# Open_Flight_Controller.net
KiCad netlist of a schematic drawn in EAGLE
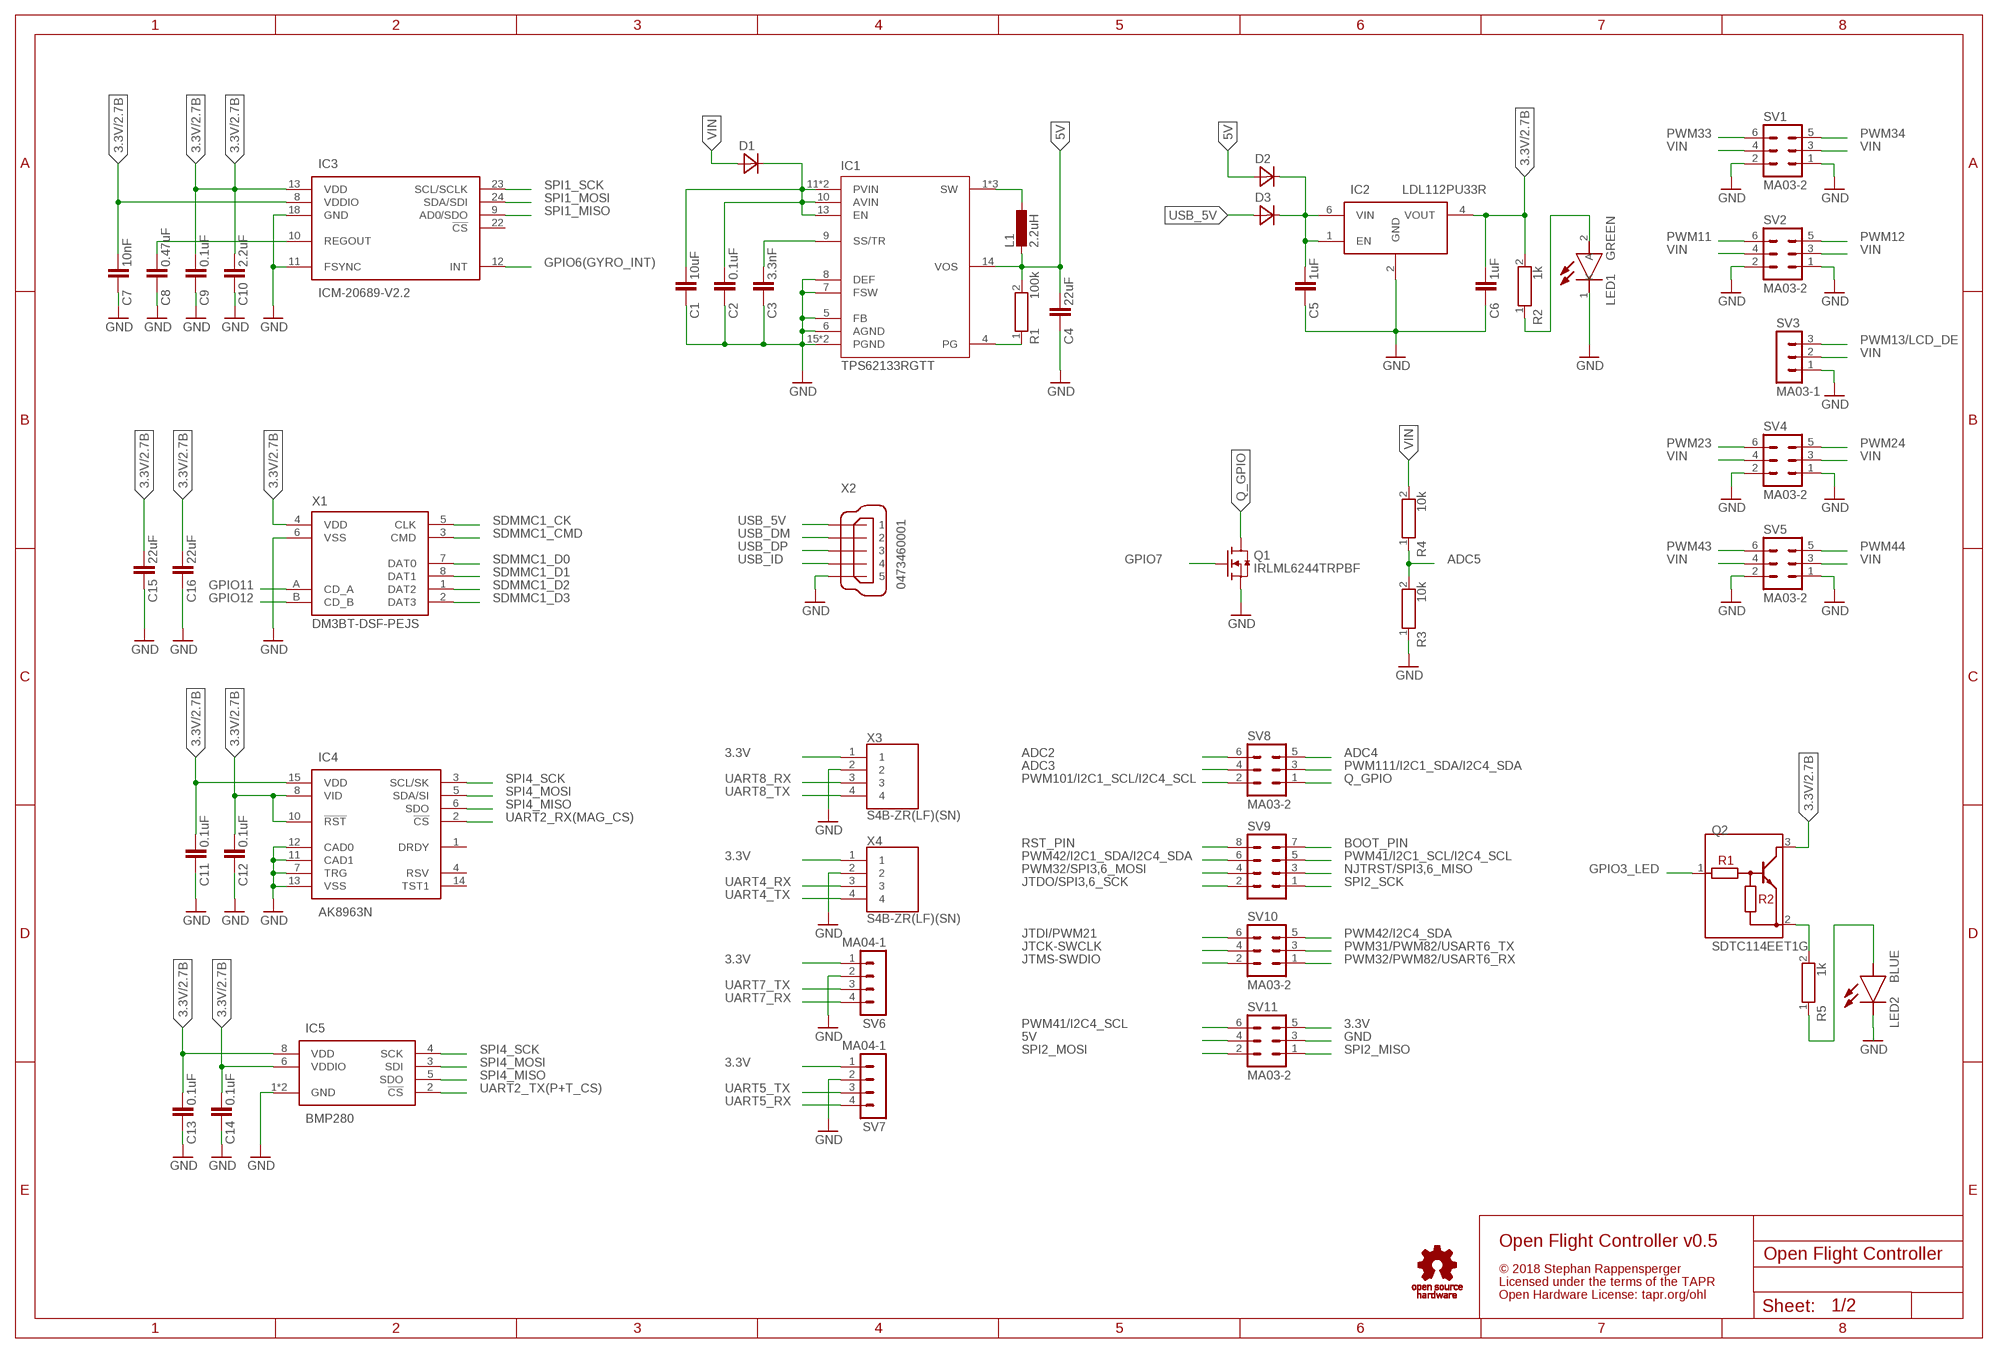
[diagram p0: schematic, sheet 1]
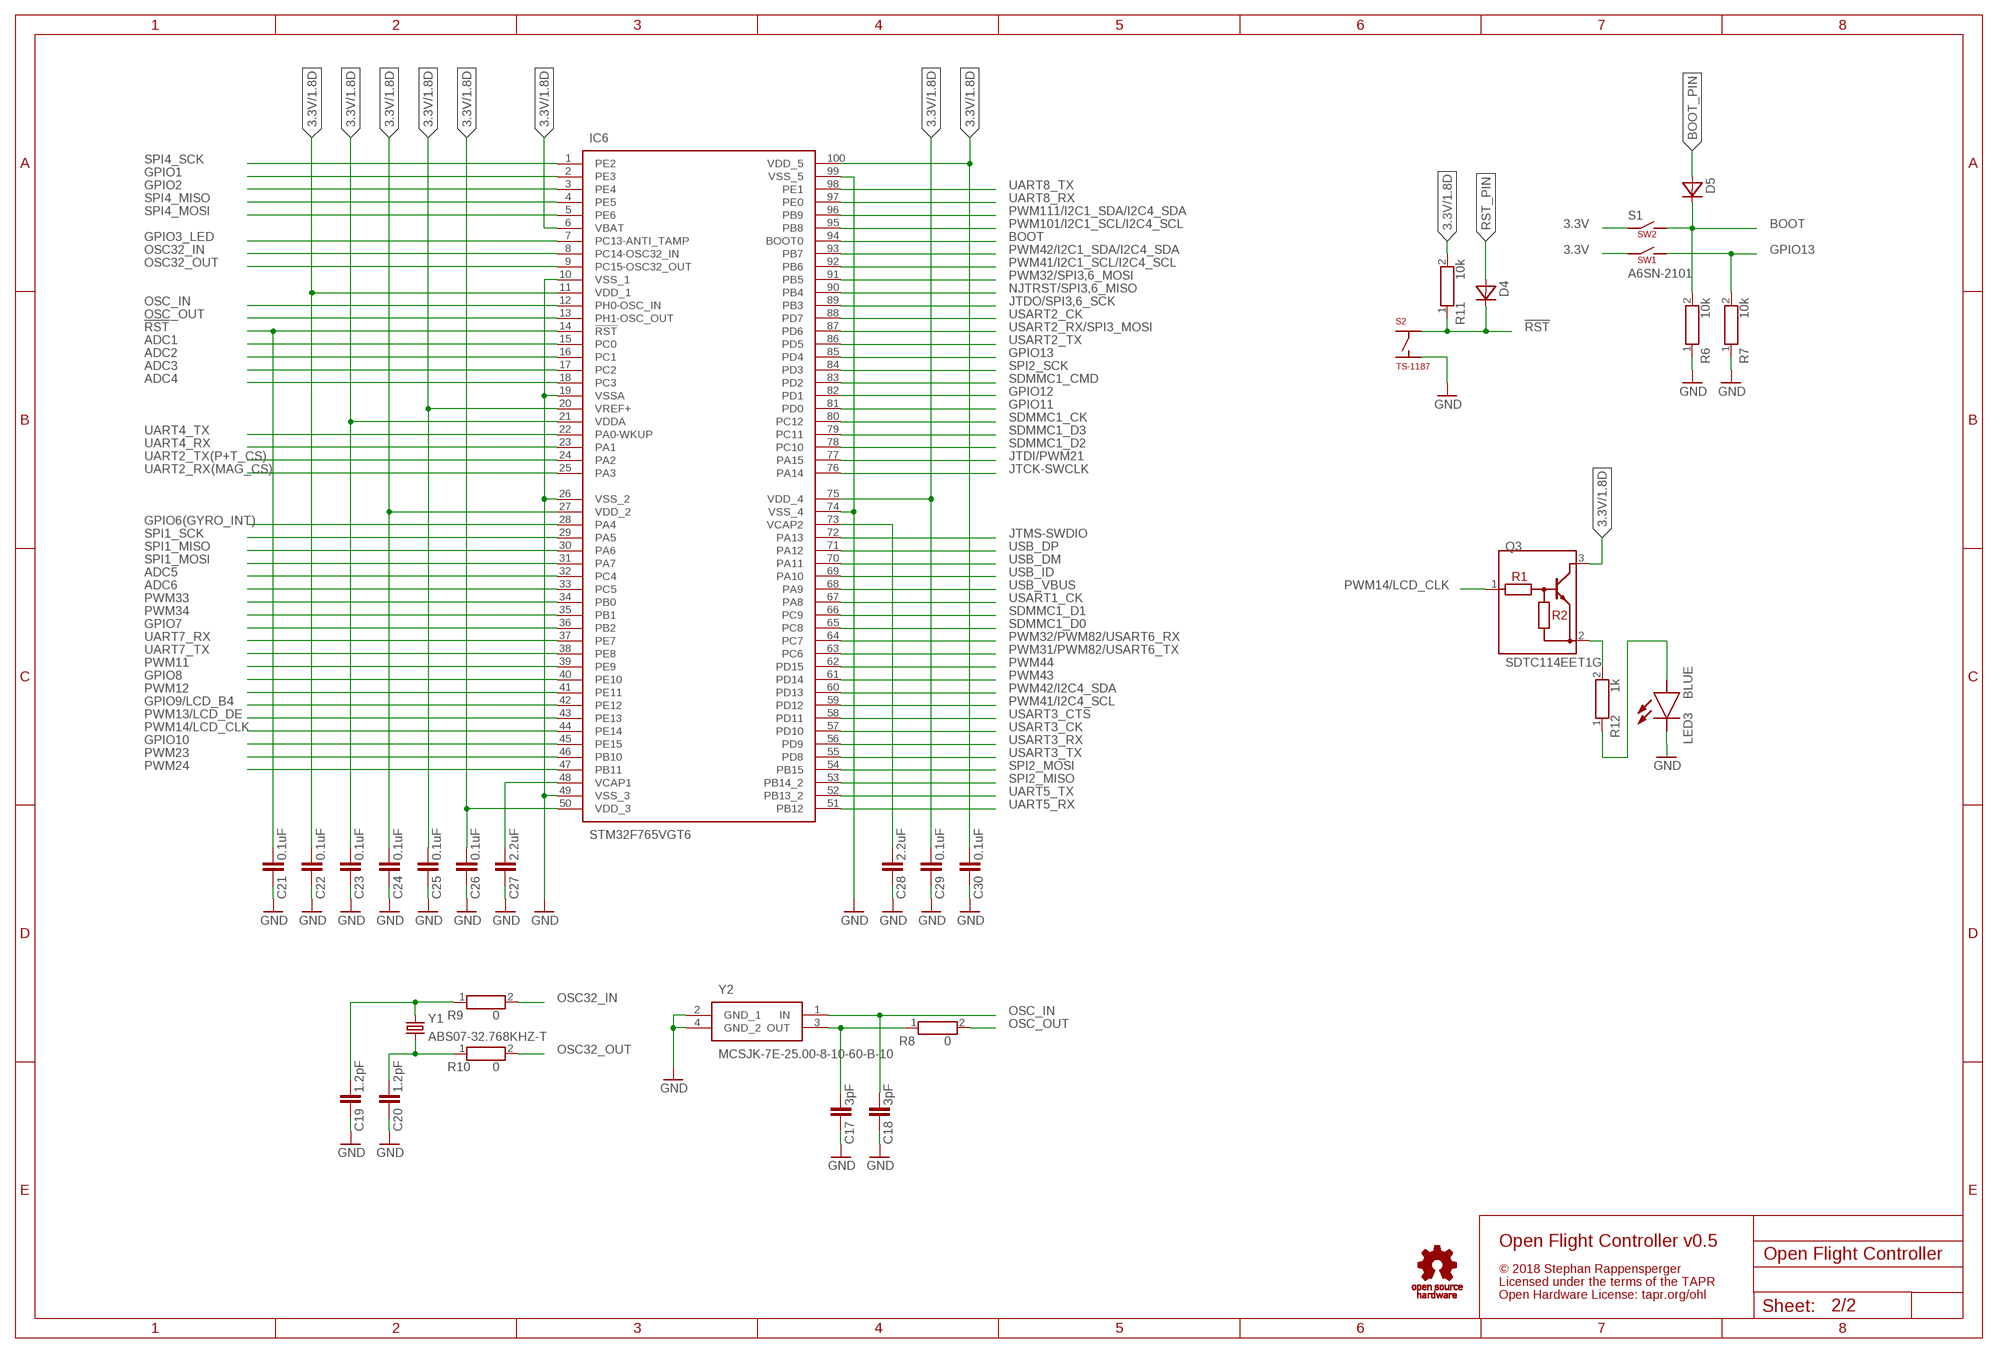
[diagram p1: schematic, sheet 2]

(export (version "E")
  (design (tool "Eeschema 10.0.6"))
  (components
    (comp (ref "C17")
      (value "3pF")
      (footprint "eagle-import:CAPC1608X90N")
      (fields
        (field (name "ARROW_PART_NUMBER") "GRM188R71C105KA12D")
        (field (name "RS_PART_NUMBER") "1448491")
      )
      (libsource (lib "eagle-import") (part "GRM188R71C105KA12D"))
    )
    (comp (ref "C18")
      (value "3pF")
      (footprint "eagle-import:CAPC1608X90N")
      (fields
        (field (name "ARROW_PART_NUMBER") "GRM188R71C105KA12D")
        (field (name "RS_PART_NUMBER") "1448491")
      )
      (libsource (lib "eagle-import") (part "GRM188R71C105KA12D"))
    )
    (comp (ref "C19")
      (value "1.2pF")
      (footprint "eagle-import:CAPC1608X90N")
      (fields
        (field (name "ARROW_PART_NUMBER") "GRM188R71C105KA12D")
        (field (name "RS_PART_NUMBER") "1448491")
      )
      (libsource (lib "eagle-import") (part "GRM188R71C105KA12D"))
    )
    (comp (ref "C20")
      (value "1.2pF")
      (footprint "eagle-import:CAPC1608X90N")
      (fields
        (field (name "ARROW_PART_NUMBER") "GRM188R71C105KA12D")
        (field (name "RS_PART_NUMBER") "1448491")
      )
      (libsource (lib "eagle-import") (part "GRM188R71C105KA12D"))
    )
    (comp (ref "C21")
      (value "0.1uF")
      (footprint "eagle-import:CAPC1608X90N")
      (fields
        (field (name "ARROW_PART_NUMBER") "GRM188R71H104KA93D")
        (field (name "RS_PART_NUMBER") "6242480P")
      )
      (libsource (lib "eagle-import") (part "GRM188R71H104KA93D"))
    )
    (comp (ref "C22")
      (value "0.1uF")
      (footprint "eagle-import:CAPC1608X90N")
      (fields
        (field (name "ARROW_PART_NUMBER") "GRM188R71H104KA93D")
        (field (name "RS_PART_NUMBER") "6242480P")
      )
      (libsource (lib "eagle-import") (part "GRM188R71H104KA93D"))
    )
    (comp (ref "C23")
      (value "0.1uF")
      (footprint "eagle-import:CAPC1608X90N")
      (fields
        (field (name "ARROW_PART_NUMBER") "GRM188R71H104KA93D")
        (field (name "RS_PART_NUMBER") "6242480P")
      )
      (libsource (lib "eagle-import") (part "GRM188R71H104KA93D"))
    )
    (comp (ref "C24")
      (value "0.1uF")
      (footprint "eagle-import:CAPC1608X90N")
      (fields
        (field (name "ARROW_PART_NUMBER") "GRM188R71H104KA93D")
        (field (name "RS_PART_NUMBER") "6242480P")
      )
      (libsource (lib "eagle-import") (part "GRM188R71H104KA93D"))
    )
    (comp (ref "C25")
      (value "0.1uF")
      (footprint "eagle-import:CAPC1608X90N")
      (fields
        (field (name "ARROW_PART_NUMBER") "GRM188R71H104KA93D")
        (field (name "RS_PART_NUMBER") "6242480P")
      )
      (libsource (lib "eagle-import") (part "GRM188R71H104KA93D"))
    )
    (comp (ref "C26")
      (value "0.1uF")
      (footprint "eagle-import:CAPC1608X90N")
      (fields
        (field (name "ARROW_PART_NUMBER") "GRM188R71H104KA93D")
        (field (name "RS_PART_NUMBER") "6242480P")
      )
      (libsource (lib "eagle-import") (part "GRM188R71H104KA93D"))
    )
    (comp (ref "C27")
      (value "2.2uF")
      (footprint "eagle-import:CAPC1608X90N")
      (fields
        (field (name "ARROW_PART_NUMBER") "GRM188R71A225KE15D")
        (field (name "RS_PART_NUMBER") "7235597P")
      )
      (libsource (lib "eagle-import") (part "GRM188R71A225KE15D"))
    )
    (comp (ref "C28")
      (value "2.2uF")
      (footprint "eagle-import:CAPC1608X90N")
      (fields
        (field (name "ARROW_PART_NUMBER") "GRM188R71A225KE15D")
        (field (name "RS_PART_NUMBER") "7235597P")
      )
      (libsource (lib "eagle-import") (part "GRM188R71A225KE15D"))
    )
    (comp (ref "C29")
      (value "0.1uF")
      (footprint "eagle-import:CAPC1608X90N")
      (fields
        (field (name "ARROW_PART_NUMBER") "GRM188R71H104KA93D")
        (field (name "RS_PART_NUMBER") "6242480P")
      )
      (libsource (lib "eagle-import") (part "GRM188R71H104KA93D"))
    )
    (comp (ref "C30")
      (value "0.1uF")
      (footprint "eagle-import:CAPC1608X90N")
      (fields
        (field (name "ARROW_PART_NUMBER") "GRM188R71H104KA93D")
        (field (name "RS_PART_NUMBER") "6242480P")
      )
      (libsource (lib "eagle-import") (part "GRM188R71H104KA93D"))
    )
    (comp (ref "D4")
      (value "RBR3MM40ATR")
      (footprint "eagle-import:PMDU")
      (fields (field (name "RS_PART_NUMBER") "1333268P"))
      (libsource (lib "eagle-import") (part "RBR3MM40ATR"))
    )
    (comp (ref "D5")
      (value "RBR3MM40ATR")
      (footprint "eagle-import:PMDU")
      (fields (field (name "RS_PART_NUMBER") "1333268P"))
      (libsource (lib "eagle-import") (part "RBR3MM40ATR"))
    )
    (comp (ref "IC6")
      (value "STM32F765VGT6")
      (footprint "eagle-import:QFP50P1600X1600X160-100N")
      (libsource (lib "eagle-import") (part "STM32F765VGT6"))
    )
    (comp (ref "LED3")
      (value "BLUE")
      (footprint "eagle-import:LEDC1608X100N")
      (fields (field (name "ARROW_PART_NUMBER") "VLMB1300-GS08") (field (name "RS_PART_NUMBER") "7730430P"))
      (libsource (lib "eagle-import") (part "VLMB1300-GS08"))
    )
    (comp (ref "Q3")
      (value "SDTC114EET1G")
      (footprint "eagle-import:SOT50P160X90-3N")
      (libsource (lib "eagle-import") (part "SDTC114EET1G"))
    )
    (comp (ref "R6")
      (value "10k")
      (footprint "eagle-import:RESC1608X50N")
      (fields (field (name "ARROW_PART_NUMBER") "CRCW060310K0FKEA") (field (name "RS_PART_NUMBER") "1694216"))
      (libsource (lib "eagle-import") (part "CRCW060310K0FKEA"))
    )
    (comp (ref "R7")
      (value "10k")
      (footprint "eagle-import:RESC1608X50N")
      (fields (field (name "ARROW_PART_NUMBER") "CRCW060310K0FKEA") (field (name "RS_PART_NUMBER") "1694216"))
      (libsource (lib "eagle-import") (part "CRCW060310K0FKEA"))
    )
    (comp (ref "R8")
      (value "0")
      (footprint "eagle-import:RESC1608X50N")
      (fields (field (name "ARROW_PART_NUMBER") "CRCW060310K0FKEA") (field (name "RS_PART_NUMBER") "1694216"))
      (libsource (lib "eagle-import") (part "CRCW060310K0FKEA"))
    )
    (comp (ref "R9")
      (value "0")
      (footprint "eagle-import:RESC1608X50N")
      (fields (field (name "ARROW_PART_NUMBER") "CRCW060310K0FKEA") (field (name "RS_PART_NUMBER") "1694216"))
      (libsource (lib "eagle-import") (part "CRCW060310K0FKEA"))
    )
    (comp (ref "R10")
      (value "0")
      (footprint "eagle-import:RESC1608X50N")
      (fields (field (name "ARROW_PART_NUMBER") "CRCW060310K0FKEA") (field (name "RS_PART_NUMBER") "1694216"))
      (libsource (lib "eagle-import") (part "CRCW060310K0FKEA"))
    )
    (comp (ref "R11")
      (value "10k")
      (footprint "eagle-import:RESC1608X50N")
      (fields (field (name "ARROW_PART_NUMBER") "CRCW060310K0FKEA") (field (name "RS_PART_NUMBER") "1694216"))
      (libsource (lib "eagle-import") (part "CRCW060310K0FKEA"))
    )
    (comp (ref "R12")
      (value "1k")
      (footprint "eagle-import:RESC1608X50N")
      (fields (field (name "ARROW_PART_NUMBER") "CRCW06031K00FKEA") (field (name "RS_PART_NUMBER") "1694265"))
      (libsource (lib "eagle-import") (part "CRCW06031K00FKEA"))
    )
    (comp (ref "S1")
      (value "A6SN-2101")
      (footprint "eagle-import:SOP254P930X455-4N")
      (libsource (lib "eagle-import") (part "A6SN-2101"))
    )
    (comp (ref "S2")
      (value "TS-1187")
      (footprint "eagle-import:TS-1187-3.8")
      (libsource (lib "eagle-import") (part "TS-1187TS-1187-H"))
    )
    (comp (ref "Y1")
      (value "ABS07-32.768KHZ-T")
      (footprint "eagle-import:ABS-07")
      (fields (field (name "RS_PART_NUMBER") "1712839"))
      (libsource (lib "eagle-import") (part "ABS07-32.768KHZ-T"))
    )
    (comp (ref "Y2")
      (value "MCSJK-7E-25.00-8-10-60-B-10")
      (footprint "eagle-import:MCSJK7E2500101060B10")
      (fields (field (name "ARROW_PART_NUMBER") "MCSJK-7E-25.00-10-10-60-B-10"))
      (libsource (lib "eagle-import") (part "MCSJK-7E-25.00-10-10-60-B-10"))
    )
    (comp (ref "C1")
      (value "10uF")
      (footprint "eagle-import:CAPC1608X90N")
      (fields
        (field (name "ARROW_PART_NUMBER") "GRM188R61E106MA73D")
        (field (name "RS_PART_NUMBER") "8151377P")
      )
      (libsource (lib "eagle-import") (part "GRM188R61E106MA73D"))
    )
    (comp (ref "C2")
      (value "0.1uF")
      (footprint "eagle-import:CAPC1608X90N")
      (fields
        (field (name "ARROW_PART_NUMBER") "GRM188R71H104KA93D")
        (field (name "RS_PART_NUMBER") "6242480P")
      )
      (libsource (lib "eagle-import") (part "GRM188R71H104KA93D"))
    )
    (comp (ref "C3")
      (value "3.3nF")
      (footprint "eagle-import:CAPC1608X90N")
      (fields
        (field (name "ARROW_PART_NUMBER") "GRM188R71H332KA01D")
        (field (name "RS_PART_NUMBER") "2040735")
      )
      (libsource (lib "eagle-import") (part "GRM188R71H332KA01D"))
    )
    (comp (ref "C4")
      (value "22uF")
      (footprint "eagle-import:CAPC1608X100N")
      (fields (field (name "ARROW_PART_NUMBER") "CL10A226KQ8NRNE"))
      (libsource (lib "eagle-import") (part "CL10A226KQ8NRNE"))
    )
    (comp (ref "C5")
      (value "1uF")
      (footprint "eagle-import:CAPC1608X90N")
      (fields
        (field (name "ARROW_PART_NUMBER") "GRM188R71C105KA12D")
        (field (name "RS_PART_NUMBER") "1448491")
      )
      (libsource (lib "eagle-import") (part "GRM188R71C105KA12D"))
    )
    (comp (ref "C6")
      (value "1uF")
      (footprint "eagle-import:CAPC1608X90N")
      (fields
        (field (name "ARROW_PART_NUMBER") "GRM188R71C105KA12D")
        (field (name "RS_PART_NUMBER") "1448491")
      )
      (libsource (lib "eagle-import") (part "GRM188R71C105KA12D"))
    )
    (comp (ref "C7")
      (value "10nF")
      (footprint "eagle-import:CAPC1608X90N")
      (fields (field (name "ARROW_PART_NUMBER") "GRM1885C1E103JA01D"))
      (libsource (lib "eagle-import") (part "GRM1885C1E103JA01D"))
    )
    (comp (ref "C8")
      (value "0.47uF")
      (footprint "eagle-import:CAPC1608X90N")
      (fields
        (field (name "ARROW_PART_NUMBER") "GRM188R71E474KA12D")
        (field (name "RS_PART_NUMBER") "1448494")
      )
      (libsource (lib "eagle-import") (part "GRM188R71E474KA12D"))
    )
    (comp (ref "C9")
      (value "0.1uF")
      (footprint "eagle-import:CAPC1608X90N")
      (fields
        (field (name "ARROW_PART_NUMBER") "GRM188R71H104KA93D")
        (field (name "RS_PART_NUMBER") "6242480P")
      )
      (libsource (lib "eagle-import") (part "GRM188R71H104KA93D"))
    )
    (comp (ref "C10")
      (value "2.2uF")
      (footprint "eagle-import:CAPC1608X90N")
      (fields
        (field (name "ARROW_PART_NUMBER") "GRM188R71A225KE15D")
        (field (name "RS_PART_NUMBER") "7235597P")
      )
      (libsource (lib "eagle-import") (part "GRM188R71A225KE15D"))
    )
    (comp (ref "C11")
      (value "0.1uF")
      (footprint "eagle-import:CAPC1608X90N")
      (fields
        (field (name "ARROW_PART_NUMBER") "GRM188R71H104KA93D")
        (field (name "RS_PART_NUMBER") "6242480P")
      )
      (libsource (lib "eagle-import") (part "GRM188R71H104KA93D"))
    )
    (comp (ref "C12")
      (value "0.1uF")
      (footprint "eagle-import:CAPC1608X90N")
      (fields
        (field (name "ARROW_PART_NUMBER") "GRM188R71H104KA93D")
        (field (name "RS_PART_NUMBER") "6242480P")
      )
      (libsource (lib "eagle-import") (part "GRM188R71H104KA93D"))
    )
    (comp (ref "C13")
      (value "0.1uF")
      (footprint "eagle-import:CAPC1608X90N")
      (fields
        (field (name "ARROW_PART_NUMBER") "GRM188R71H104KA93D")
        (field (name "RS_PART_NUMBER") "6242480P")
      )
      (libsource (lib "eagle-import") (part "GRM188R71H104KA93D"))
    )
    (comp (ref "C14")
      (value "0.1uF")
      (footprint "eagle-import:CAPC1608X90N")
      (fields
        (field (name "ARROW_PART_NUMBER") "GRM188R71H104KA93D")
        (field (name "RS_PART_NUMBER") "6242480P")
      )
      (libsource (lib "eagle-import") (part "GRM188R71H104KA93D"))
    )
    (comp (ref "C15")
      (value "22uF")
      (footprint "eagle-import:CAPC1608X100N")
      (fields (field (name "ARROW_PART_NUMBER") "CL10A226KQ8NRNE"))
      (libsource (lib "eagle-import") (part "CL10A226KQ8NRNE"))
    )
    (comp (ref "C16")
      (value "22uF")
      (footprint "eagle-import:CAPC1608X100N")
      (fields (field (name "ARROW_PART_NUMBER") "CL10A226KQ8NRNE"))
      (libsource (lib "eagle-import") (part "CL10A226KQ8NRNE"))
    )
    (comp (ref "D1")
      (value "RBR3MM40ATR")
      (footprint "eagle-import:PMDU")
      (fields (field (name "RS_PART_NUMBER") "1333268P"))
      (libsource (lib "eagle-import") (part "RBR3MM40ATR"))
    )
    (comp (ref "D2")
      (value "RBR3MM40ATR")
      (footprint "eagle-import:PMDU")
      (fields (field (name "RS_PART_NUMBER") "1333268P"))
      (libsource (lib "eagle-import") (part "RBR3MM40ATR"))
    )
    (comp (ref "D3")
      (value "RBR3MM40ATR")
      (footprint "eagle-import:PMDU")
      (fields (field (name "RS_PART_NUMBER") "1333268P"))
      (libsource (lib "eagle-import") (part "RBR3MM40ATR"))
    )
    (comp (ref "IC1")
      (value "TPS62133RGTT")
      (footprint "eagle-import:RGT16_1P7X1P7")
      (libsource (lib "eagle-import") (part "TPS62133RGTT"))
    )
    (comp (ref "IC2")
      (value "LDL112PU33R")
      (footprint "eagle-import:SON50P200X200X80-7N")
      (libsource (lib "eagle-import") (part "LDL112PU33R"))
    )
    (comp (ref "IC3")
      (value "ICM-20689-V2.2")
      (footprint "eagle-import:QFN50P400X400X95-25N")
      (fields (field (name "ARROW_PART_NUMBER") "ICM-20689-v1.0"))
      (libsource (lib "eagle-import") (part "ICM-20689-V2.2"))
    )
    (comp (ref "IC4")
      (value "AK8963N")
      (footprint "eagle-import:QFN50P300X300X80-17N")
      (libsource (lib "eagle-import") (part "AK8963N"))
    )
    (comp (ref "IC5")
      (value "BMP280")
      (footprint "eagle-import:8-PIN-METAL-LID-LGA")
      (fields (field (name "ARROW_PART_NUMBER") "bmp280"))
      (libsource (lib "eagle-import") (part "BMP280"))
    )
    (comp (ref "L1")
      (value "2.2uH")
      (footprint "eagle-import:INDC2520X120N")
      (fields
        (field (name "ARROW_PART_NUMBER") "DFE252012P-2R2M=P2")
        (field (name "RS_PART_NUMBER") "1670606")
      )
      (libsource (lib "eagle-import") (part "DFE252012P-2R2M=P2"))
    )
    (comp (ref "LED1")
      (value "GREEN")
      (footprint "eagle-import:LEDC1608X100N")
      (fields (field (name "ARROW_PART_NUMBER") "VLMG1300-GS08") (field (name "RS_PART_NUMBER") "1652940"))
      (libsource (lib "eagle-import") (part "VLMG1300-GS08"))
    )
    (comp (ref "LED2")
      (value "BLUE")
      (footprint "eagle-import:LEDC1608X100N")
      (fields (field (name "ARROW_PART_NUMBER") "VLMB1300-GS08") (field (name "RS_PART_NUMBER") "7730430P"))
      (libsource (lib "eagle-import") (part "VLMB1300-GS08"))
    )
    (comp (ref "Q1")
      (value "IRLML6244TRPBF")
      (footprint "eagle-import:SOT95P237X112-3N")
      (fields (field (name "RS_PART_NUMBER") "7377228"))
      (libsource (lib "eagle-import") (part "IRLML6244TRPBF"))
    )
    (comp (ref "Q2")
      (value "SDTC114EET1G")
      (footprint "eagle-import:SOT50P160X90-3N")
      (libsource (lib "eagle-import") (part "SDTC114EET1G"))
    )
    (comp (ref "R1")
      (value "100k")
      (footprint "eagle-import:RESC1608X50N")
      (fields (field (name "ARROW_PART_NUMBER") "CRCW0603100KFKEA") (field (name "RS_PART_NUMBER") "1694218"))
      (libsource (lib "eagle-import") (part "CRCW0603100KFKEA"))
    )
    (comp (ref "R2")
      (value "1k")
      (footprint "eagle-import:RESC1608X50N")
      (fields (field (name "ARROW_PART_NUMBER") "CRCW06031K00FKEA") (field (name "RS_PART_NUMBER") "1694265"))
      (libsource (lib "eagle-import") (part "CRCW06031K00FKEA"))
    )
    (comp (ref "R3")
      (value "10k")
      (footprint "eagle-import:RESC1608X50N")
      (fields (field (name "ARROW_PART_NUMBER") "CRCW060310K0FKEA") (field (name "RS_PART_NUMBER") "1694216"))
      (libsource (lib "eagle-import") (part "CRCW060310K0FKEA"))
    )
    (comp (ref "R4")
      (value "10k")
      (footprint "eagle-import:RESC1608X50N")
      (fields (field (name "ARROW_PART_NUMBER") "CRCW060310K0FKEA") (field (name "RS_PART_NUMBER") "1694216"))
      (libsource (lib "eagle-import") (part "CRCW060310K0FKEA"))
    )
    (comp (ref "R5")
      (value "1k")
      (footprint "eagle-import:RESC1608X50N")
      (fields (field (name "ARROW_PART_NUMBER") "CRCW06031K00FKEA") (field (name "RS_PART_NUMBER") "1694265"))
      (libsource (lib "eagle-import") (part "CRCW06031K00FKEA"))
    )
    (comp (ref "SV1")
      (value "MA03-2")
      (footprint "eagle-import:MA03-2")
      (libsource (lib "eagle-import") (part "MA03-2"))
    )
    (comp (ref "SV2")
      (value "MA03-2")
      (footprint "eagle-import:MA03-2")
      (libsource (lib "eagle-import") (part "MA03-2"))
    )
    (comp (ref "SV3")
      (value "MA03-1")
      (footprint "eagle-import:MA03-1")
      (libsource (lib "eagle-import") (part "MA03-1"))
    )
    (comp (ref "SV4")
      (value "MA03-2")
      (footprint "eagle-import:MA03-2")
      (libsource (lib "eagle-import") (part "MA03-2"))
    )
    (comp (ref "SV5")
      (value "MA03-2")
      (footprint "eagle-import:MA03-2")
      (libsource (lib "eagle-import") (part "MA03-2"))
    )
    (comp (ref "SV6")
      (value "MA04-1")
      (footprint "eagle-import:MA04-1")
      (libsource (lib "eagle-import") (part "MA04-1"))
    )
    (comp (ref "SV7")
      (value "MA04-1")
      (footprint "eagle-import:MA04-1")
      (libsource (lib "eagle-import") (part "MA04-1"))
    )
    (comp (ref "SV8")
      (value "MA03-2")
      (footprint "eagle-import:MA03-2")
      (libsource (lib "eagle-import") (part "MA03-2"))
    )
    (comp (ref "SV9")
      (value "MA04-2")
      (footprint "eagle-import:MA04-2")
      (libsource (lib "eagle-import") (part "MA04-2"))
    )
    (comp (ref "SV10")
      (value "MA03-2")
      (footprint "eagle-import:MA03-2")
      (libsource (lib "eagle-import") (part "MA03-2"))
    )
    (comp (ref "SV11")
      (value "MA03-2")
      (footprint "eagle-import:MA03-2")
      (libsource (lib "eagle-import") (part "MA03-2"))
    )
    (comp (ref "X1")
      (value "DM3BT-DSF-PEJS")
      (footprint "eagle-import:DM3BT-DSF-PEJS")
      (libsource (lib "eagle-import") (part "DM3BT-DSF-PEJS"))
    )
    (comp (ref "X2")
      (value "0473460001")
      (footprint "eagle-import:0473460001")
      (libsource (lib "eagle-import") (part "0473460001"))
    )
    (comp (ref "X3")
      (value "S4B-ZR(LF)(SN)")
      (footprint "eagle-import:SHDR4W50P0X150_1X4_750X600X370")
      (fields (field (name "ARROW_PART_NUMBER") "S4B-ZR  (LF)(SN)") (field (name "RS_PART_NUMBER") "1724917"))
      (libsource (lib "eagle-import") (part "S4B-ZR(LF)(SN)"))
    )
    (comp (ref "X4")
      (value "S4B-ZR(LF)(SN)")
      (footprint "eagle-import:SHDR4W50P0X150_1X4_750X600X370")
      (fields (field (name "ARROW_PART_NUMBER") "S4B-ZR  (LF)(SN)") (field (name "RS_PART_NUMBER") "1724917"))
      (libsource (lib "eagle-import") (part "S4B-ZR(LF)(SN)"))
    )
  )
  (nets
    (net (code "1") (name "3.3V") (class "Default")
      (node (ref "C10") (pin "1") (pinfunction "P$1_1") (pintype "bidirectional"))
      (node (ref "C11") (pin "1") (pinfunction "P$1_1") (pintype "bidirectional"))
      (node (ref "C12") (pin "1") (pinfunction "P$1_1") (pintype "bidirectional"))
      (node (ref "C13") (pin "1") (pinfunction "P$1_1") (pintype "bidirectional"))
      (node (ref "C14") (pin "1") (pinfunction "P$1_1") (pintype "bidirectional"))
      (node (ref "C15") (pin "1") (pinfunction "P$1_1") (pintype "bidirectional"))
      (node (ref "C16") (pin "1") (pinfunction "P$1_1") (pintype "bidirectional"))
      (node (ref "C22") (pin "1") (pinfunction "P$1_1") (pintype "bidirectional"))
      (node (ref "C23") (pin "1") (pinfunction "P$1_1") (pintype "bidirectional"))
      (node (ref "C24") (pin "1") (pinfunction "P$1_1") (pintype "bidirectional"))
      (node (ref "C25") (pin "1") (pinfunction "P$1_1") (pintype "bidirectional"))
      (node (ref "C26") (pin "1") (pinfunction "P$1_1") (pintype "bidirectional"))
      (node (ref "C29") (pin "1") (pinfunction "P$1_1") (pintype "bidirectional"))
      (node (ref "C30") (pin "1") (pinfunction "P$1_1") (pintype "bidirectional"))
      (node (ref "C6") (pin "1") (pinfunction "P$1_1") (pintype "bidirectional"))
      (node (ref "C7") (pin "1") (pinfunction "P$1_1") (pintype "bidirectional"))
      (node (ref "C9") (pin "1") (pinfunction "P$1_1") (pintype "bidirectional"))
      (node (ref "IC2") (pin "4") (pinfunction "VOUT_4") (pintype "bidirectional"))
      (node (ref "IC3") (pin "13") (pinfunction "VDD_13") (pintype "bidirectional"))
      (node (ref "IC3") (pin "8") (pinfunction "VDDIO_8") (pintype "bidirectional"))
      (node (ref "IC4") (pin "10") (pinfunction "~{RST}_10") (pintype "bidirectional"))
      (node (ref "IC4") (pin "15") (pinfunction "VDD_15") (pintype "bidirectional"))
      (node (ref "IC4") (pin "8") (pinfunction "VID_8") (pintype "bidirectional"))
      (node (ref "IC5") (pin "6") (pinfunction "VDDIO_6") (pintype "power_in"))
      (node (ref "IC5") (pin "8") (pinfunction "VDD_8") (pintype "power_in"))
      (node (ref "IC6") (pin "100") (pinfunction "VDD_5_100") (pintype "bidirectional"))
      (node (ref "IC6") (pin "11") (pinfunction "VDD_1_11") (pintype "bidirectional"))
      (node (ref "IC6") (pin "20") (pinfunction "VREF+_20") (pintype "bidirectional"))
      (node (ref "IC6") (pin "21") (pinfunction "VDDA_21") (pintype "bidirectional"))
      (node (ref "IC6") (pin "27") (pinfunction "VDD_2_27") (pintype "bidirectional"))
      (node (ref "IC6") (pin "50") (pinfunction "VDD_3_50") (pintype "bidirectional"))
      (node (ref "IC6") (pin "6") (pinfunction "VBAT_6") (pintype "bidirectional"))
      (node (ref "IC6") (pin "75") (pinfunction "VDD_4_75") (pintype "bidirectional"))
      (node (ref "Q2") (pin "3") (pinfunction "C_3") (pintype "output"))
      (node (ref "Q3") (pin "3") (pinfunction "C_3") (pintype "output"))
      (node (ref "R11") (pin "2") (pinfunction "2_2") (pintype "bidirectional"))
      (node (ref "R2") (pin "2") (pinfunction "2_2") (pintype "bidirectional"))
      (node (ref "S1") (pin "1") (pinfunction "COM_1_1") (pintype "bidirectional"))
      (node (ref "S1") (pin "2") (pinfunction "COM_2_2") (pintype "bidirectional"))
      (node (ref "SV11") (pin "5") (pinfunction "5_5") (pintype "passive"))
      (node (ref "SV6") (pin "1") (pinfunction "1_1") (pintype "passive"))
      (node (ref "SV7") (pin "1") (pinfunction "1_1") (pintype "passive"))
      (node (ref "X1") (pin "4") (pinfunction "VDD_4") (pintype "bidirectional"))
      (node (ref "X3") (pin "1") (pinfunction "1_1") (pintype "bidirectional"))
      (node (ref "X4") (pin "1") (pinfunction "1_1") (pintype "bidirectional"))
    )
    (net (code "2") (name "5V") (class "Default")
      (node (ref "C4") (pin "1") (pinfunction "P$1_1") (pintype "bidirectional"))
      (node (ref "D2") (pin "1") (pinfunction "A_1") (pintype "passive"))
      (node (ref "IC1") (pin "14") (pinfunction "VOS_14") (pintype "input"))
      (node (ref "L1") (pin "1") (pinfunction "1_1") (pintype "passive"))
      (node (ref "R1") (pin "2") (pinfunction "2_2") (pintype "bidirectional"))
      (node (ref "SV11") (pin "4") (pinfunction "4_4") (pintype "passive"))
    )
    (net (code "3") (name "ADC1") (class "Default")
      (node (ref "IC6") (pin "15") (pinfunction "PC0_15") (pintype "bidirectional"))
    )
    (net (code "4") (name "ADC2") (class "Default")
      (node (ref "IC6") (pin "16") (pinfunction "PC1_16") (pintype "bidirectional"))
      (node (ref "SV8") (pin "6") (pinfunction "6_6") (pintype "passive"))
    )
    (net (code "5") (name "ADC3") (class "Default")
      (node (ref "IC6") (pin "17") (pinfunction "PC2_17") (pintype "bidirectional"))
      (node (ref "SV8") (pin "4") (pinfunction "4_4") (pintype "passive"))
    )
    (net (code "6") (name "ADC4") (class "Default")
      (node (ref "IC6") (pin "18") (pinfunction "PC3_18") (pintype "bidirectional"))
      (node (ref "SV8") (pin "5") (pinfunction "5_5") (pintype "passive"))
    )
    (net (code "7") (name "ADC5") (class "Default")
      (node (ref "IC6") (pin "32") (pinfunction "PC4_32") (pintype "bidirectional"))
      (node (ref "R3") (pin "2") (pinfunction "2_2") (pintype "bidirectional"))
      (node (ref "R4") (pin "1") (pinfunction "1_1") (pintype "bidirectional"))
    )
    (net (code "8") (name "ADC6") (class "Default")
      (node (ref "IC6") (pin "33") (pinfunction "PC5_33") (pintype "bidirectional"))
    )
    (net (code "9") (name "BOOT") (class "Default")
      (node (ref "D5") (pin "2") (pinfunction "C_2") (pintype "passive"))
      (node (ref "IC6") (pin "94") (pinfunction "BOOT0_94") (pintype "bidirectional"))
      (node (ref "R6") (pin "2") (pinfunction "2_2") (pintype "bidirectional"))
      (node (ref "S1") (pin "4") (pinfunction "NO_1_4") (pintype "bidirectional"))
    )
    (net (code "10") (name "BOOT_PIN") (class "Default")
      (node (ref "D5") (pin "1") (pinfunction "A_1") (pintype "passive"))
      (node (ref "SV9") (pin "7") (pinfunction "7_7") (pintype "passive"))
    )
    (net (code "11") (name "GND") (class "Default")
      (node (ref "C1") (pin "2") (pinfunction "P$2_2") (pintype "bidirectional"))
      (node (ref "C10") (pin "2") (pinfunction "P$2_2") (pintype "bidirectional"))
      (node (ref "C11") (pin "2") (pinfunction "P$2_2") (pintype "bidirectional"))
      (node (ref "C12") (pin "2") (pinfunction "P$2_2") (pintype "bidirectional"))
      (node (ref "C13") (pin "2") (pinfunction "P$2_2") (pintype "bidirectional"))
      (node (ref "C14") (pin "2") (pinfunction "P$2_2") (pintype "bidirectional"))
      (node (ref "C15") (pin "2") (pinfunction "P$2_2") (pintype "bidirectional"))
      (node (ref "C16") (pin "2") (pinfunction "P$2_2") (pintype "bidirectional"))
      (node (ref "C17") (pin "2") (pinfunction "P$2_2") (pintype "bidirectional"))
      (node (ref "C18") (pin "2") (pinfunction "P$2_2") (pintype "bidirectional"))
      (node (ref "C19") (pin "2") (pinfunction "P$2_2") (pintype "bidirectional"))
      (node (ref "C2") (pin "2") (pinfunction "P$2_2") (pintype "bidirectional"))
      (node (ref "C20") (pin "2") (pinfunction "P$2_2") (pintype "bidirectional"))
      (node (ref "C21") (pin "2") (pinfunction "P$2_2") (pintype "bidirectional"))
      (node (ref "C22") (pin "2") (pinfunction "P$2_2") (pintype "bidirectional"))
      (node (ref "C23") (pin "2") (pinfunction "P$2_2") (pintype "bidirectional"))
      (node (ref "C24") (pin "2") (pinfunction "P$2_2") (pintype "bidirectional"))
      (node (ref "C25") (pin "2") (pinfunction "P$2_2") (pintype "bidirectional"))
      (node (ref "C26") (pin "2") (pinfunction "P$2_2") (pintype "bidirectional"))
      (node (ref "C27") (pin "2") (pinfunction "P$2_2") (pintype "bidirectional"))
      (node (ref "C28") (pin "2") (pinfunction "P$2_2") (pintype "bidirectional"))
      (node (ref "C29") (pin "2") (pinfunction "P$2_2") (pintype "bidirectional"))
      (node (ref "C3") (pin "2") (pinfunction "P$2_2") (pintype "bidirectional"))
      (node (ref "C30") (pin "2") (pinfunction "P$2_2") (pintype "bidirectional"))
      (node (ref "C4") (pin "2") (pinfunction "P$2_2") (pintype "bidirectional"))
      (node (ref "C5") (pin "2") (pinfunction "P$2_2") (pintype "bidirectional"))
      (node (ref "C6") (pin "2") (pinfunction "P$2_2") (pintype "bidirectional"))
      (node (ref "C7") (pin "2") (pinfunction "P$2_2") (pintype "bidirectional"))
      (node (ref "C8") (pin "2") (pinfunction "P$2_2") (pintype "bidirectional"))
      (node (ref "C9") (pin "2") (pinfunction "P$2_2") (pintype "bidirectional"))
      (node (ref "IC1") (pin "15") (pinfunction "PGND_15") (pintype "power_in"))
      (node (ref "IC1") (pin "16") (pinfunction "PGND_16") (pintype "power_in"))
      (node (ref "IC1") (pin "5") (pinfunction "FB_5") (pintype "input"))
      (node (ref "IC1") (pin "6") (pinfunction "AGND_6") (pintype "power_in"))
      (node (ref "IC1") (pin "7") (pinfunction "FSW_7") (pintype "input"))
      (node (ref "IC1") (pin "8") (pinfunction "DEF_8") (pintype "input"))
      (node (ref "IC2") (pin "2") (pinfunction "GND_2") (pintype "bidirectional"))
      (node (ref "IC3") (pin "11") (pinfunction "FSYNC_11") (pintype "bidirectional"))
      (node (ref "IC3") (pin "18") (pinfunction "GND_18") (pintype "bidirectional"))
      (node (ref "IC4") (pin "11") (pinfunction "CAD1_11") (pintype "bidirectional"))
      (node (ref "IC4") (pin "12") (pinfunction "CAD0_12") (pintype "bidirectional"))
      (node (ref "IC4") (pin "13") (pinfunction "VSS_13") (pintype "bidirectional"))
      (node (ref "IC4") (pin "7") (pinfunction "TRG_7") (pintype "bidirectional"))
      (node (ref "IC5") (pin "1") (pinfunction "GND_1") (pintype "power_in"))
      (node (ref "IC5") (pin "7") (pinfunction "GND_7") (pintype "power_in"))
      (node (ref "IC6") (pin "10") (pinfunction "VSS_1_10") (pintype "bidirectional"))
      (node (ref "IC6") (pin "19") (pinfunction "VSSA_19") (pintype "bidirectional"))
      (node (ref "IC6") (pin "26") (pinfunction "VSS_2_26") (pintype "bidirectional"))
      (node (ref "IC6") (pin "49") (pinfunction "VSS_3_49") (pintype "bidirectional"))
      (node (ref "IC6") (pin "74") (pinfunction "VSS_4_74") (pintype "bidirectional"))
      (node (ref "IC6") (pin "99") (pinfunction "VSS_5_99") (pintype "bidirectional"))
      (node (ref "LED1") (pin "1") (pinfunction "K_1") (pintype "bidirectional"))
      (node (ref "LED2") (pin "1") (pinfunction "K_1") (pintype "bidirectional"))
      (node (ref "LED3") (pin "1") (pinfunction "K_1") (pintype "bidirectional"))
      (node (ref "Q1") (pin "2") (pinfunction "S_2") (pintype "passive"))
      (node (ref "R3") (pin "1") (pinfunction "1_1") (pintype "bidirectional"))
      (node (ref "R6") (pin "1") (pinfunction "1_1") (pintype "bidirectional"))
      (node (ref "R7") (pin "1") (pinfunction "1_1") (pintype "bidirectional"))
      (node (ref "S2") (pin "P$4") (pinfunction "P$4_P$4") (pintype "bidirectional"))
      (node (ref "SV1") (pin "1") (pinfunction "1_1") (pintype "passive"))
      (node (ref "SV1") (pin "2") (pinfunction "2_2") (pintype "passive"))
      (node (ref "SV11") (pin "3") (pinfunction "3_3") (pintype "passive"))
      (node (ref "SV2") (pin "1") (pinfunction "1_1") (pintype "passive"))
      (node (ref "SV2") (pin "2") (pinfunction "2_2") (pintype "passive"))
      (node (ref "SV3") (pin "1") (pinfunction "1_1") (pintype "passive"))
      (node (ref "SV4") (pin "1") (pinfunction "1_1") (pintype "passive"))
      (node (ref "SV4") (pin "2") (pinfunction "2_2") (pintype "passive"))
      (node (ref "SV5") (pin "1") (pinfunction "1_1") (pintype "passive"))
      (node (ref "SV5") (pin "2") (pinfunction "2_2") (pintype "passive"))
      (node (ref "SV6") (pin "2") (pinfunction "2_2") (pintype "passive"))
      (node (ref "SV7") (pin "2") (pinfunction "2_2") (pintype "passive"))
      (node (ref "X1") (pin "6") (pinfunction "VSS_6") (pintype "bidirectional"))
      (node (ref "X2") (pin "5") (pinfunction "5_5") (pintype "input"))
      (node (ref "X3") (pin "2") (pinfunction "2_2") (pintype "bidirectional"))
      (node (ref "X4") (pin "2") (pinfunction "2_2") (pintype "bidirectional"))
      (node (ref "Y2") (pin "2") (pinfunction "GND_1_2") (pintype "bidirectional"))
      (node (ref "Y2") (pin "4") (pinfunction "GND_2_4") (pintype "bidirectional"))
    )
    (net (code "12") (name "GPIO1") (class "Default")
      (node (ref "IC6") (pin "2") (pinfunction "PE3_2") (pintype "bidirectional"))
    )
    (net (code "13") (name "GPIO2") (class "Default")
      (node (ref "IC6") (pin "3") (pinfunction "PE4_3") (pintype "bidirectional"))
    )
    (net (code "14") (name "GPIO3_LED") (class "Default")
      (node (ref "IC6") (pin "7") (pinfunction "PC13-ANTI_TAMP_7") (pintype "bidirectional"))
      (node (ref "Q2") (pin "1") (pinfunction "B_1") (pintype "input"))
    )
    (net (code "15") (name "GPIO6(GYRO_INT)") (class "Default")
      (node (ref "IC3") (pin "12") (pinfunction "INT_12") (pintype "bidirectional"))
      (node (ref "IC6") (pin "28") (pinfunction "PA4_28") (pintype "bidirectional"))
    )
    (net (code "16") (name "GPIO7") (class "Default")
      (node (ref "IC6") (pin "36") (pinfunction "PB2_36") (pintype "bidirectional"))
      (node (ref "Q1") (pin "1") (pinfunction "G_1") (pintype "passive"))
    )
    (net (code "17") (name "GPIO8") (class "Default")
      (node (ref "IC6") (pin "40") (pinfunction "PE10_40") (pintype "bidirectional"))
    )
    (net (code "18") (name "GPIO9{slash}LCD_B4") (class "Default")
      (node (ref "IC6") (pin "42") (pinfunction "PE12_42") (pintype "bidirectional"))
    )
    (net (code "19") (name "GPIO10") (class "Default")
      (node (ref "IC6") (pin "45") (pinfunction "PE15_45") (pintype "bidirectional"))
    )
    (net (code "20") (name "GPIO11") (class "Default")
      (node (ref "IC6") (pin "81") (pinfunction "PD0_81") (pintype "bidirectional"))
      (node (ref "X1") (pin "A") (pinfunction "CD_A_A") (pintype "bidirectional"))
    )
    (net (code "21") (name "GPIO12") (class "Default")
      (node (ref "IC6") (pin "82") (pinfunction "PD1_82") (pintype "bidirectional"))
      (node (ref "X1") (pin "B") (pinfunction "CD_B_B") (pintype "bidirectional"))
    )
    (net (code "22") (name "GPIO13") (class "Default")
      (node (ref "IC6") (pin "85") (pinfunction "PD4_85") (pintype "bidirectional"))
      (node (ref "R7") (pin "2") (pinfunction "2_2") (pintype "bidirectional"))
      (node (ref "S1") (pin "3") (pinfunction "NO_2_3") (pintype "bidirectional"))
    )
    (net (code "23") (name "JTCK-SWCLK") (class "Default")
      (node (ref "IC6") (pin "76") (pinfunction "PA14_76") (pintype "bidirectional"))
      (node (ref "SV10") (pin "4") (pinfunction "4_4") (pintype "passive"))
    )
    (net (code "24") (name "JTDI{slash}PWM21") (class "Default")
      (node (ref "IC6") (pin "77") (pinfunction "PA15_77") (pintype "bidirectional"))
      (node (ref "SV10") (pin "6") (pinfunction "6_6") (pintype "passive"))
    )
    (net (code "25") (name "JTDO{slash}SPI3,6_SCK") (class "Default")
      (node (ref "IC6") (pin "89") (pinfunction "PB3_89") (pintype "bidirectional"))
      (node (ref "SV9") (pin "2") (pinfunction "2_2") (pintype "passive"))
    )
    (net (code "26") (name "JTMS-SWDIO") (class "Default")
      (node (ref "IC6") (pin "72") (pinfunction "PA13_72") (pintype "bidirectional"))
      (node (ref "SV10") (pin "2") (pinfunction "2_2") (pintype "passive"))
    )
    (net (code "27") (name "NJTRST{slash}SPI3,6_MISO") (class "Default")
      (node (ref "IC6") (pin "90") (pinfunction "PB4_90") (pintype "bidirectional"))
      (node (ref "SV9") (pin "3") (pinfunction "3_3") (pintype "passive"))
    )
    (net (code "28") (name "Net-(C1-P$1)") (class "Default")
      (node (ref "C1") (pin "1") (pinfunction "P$1_1") (pintype "bidirectional"))
      (node (ref "C2") (pin "1") (pinfunction "P$1_1") (pintype "bidirectional"))
      (node (ref "D1") (pin "2") (pinfunction "C_2") (pintype "passive"))
      (node (ref "IC1") (pin "10") (pinfunction "AVIN_10") (pintype "input"))
      (node (ref "IC1") (pin "11") (pinfunction "PVIN_11") (pintype "input"))
      (node (ref "IC1") (pin "12") (pinfunction "PVIN_12") (pintype "input"))
      (node (ref "IC1") (pin "13") (pinfunction "EN_13") (pintype "input"))
    )
    (net (code "29") (name "Net-(C3-P$1)") (class "Default")
      (node (ref "C3") (pin "1") (pinfunction "P$1_1") (pintype "bidirectional"))
      (node (ref "IC1") (pin "9") (pinfunction "SS/TR_9") (pintype "input"))
    )
    (net (code "30") (name "Net-(C5-P$1)") (class "Default")
      (node (ref "C5") (pin "1") (pinfunction "P$1_1") (pintype "bidirectional"))
      (node (ref "D2") (pin "2") (pinfunction "C_2") (pintype "passive"))
      (node (ref "D3") (pin "2") (pinfunction "C_2") (pintype "passive"))
      (node (ref "IC2") (pin "1") (pinfunction "EN_1") (pintype "bidirectional"))
      (node (ref "IC2") (pin "6") (pinfunction "VIN_6") (pintype "bidirectional"))
    )
    (net (code "31") (name "Net-(C8-P$1)") (class "Default")
      (node (ref "C8") (pin "1") (pinfunction "P$1_1") (pintype "bidirectional"))
      (node (ref "IC3") (pin "10") (pinfunction "REGOUT_10") (pintype "bidirectional"))
    )
    (net (code "32") (name "Net-(C17-P$1)") (class "Default")
      (node (ref "C17") (pin "1") (pinfunction "P$1_1") (pintype "bidirectional"))
      (node (ref "R8") (pin "1") (pinfunction "1_1") (pintype "bidirectional"))
      (node (ref "Y2") (pin "3") (pinfunction "OUT_3") (pintype "bidirectional"))
    )
    (net (code "33") (name "Net-(C19-P$1)") (class "Default")
      (node (ref "C19") (pin "1") (pinfunction "P$1_1") (pintype "bidirectional"))
      (node (ref "R9") (pin "1") (pinfunction "1_1") (pintype "bidirectional"))
      (node (ref "Y1") (pin "1") (pinfunction "1_1") (pintype "passive"))
    )
    (net (code "34") (name "Net-(C20-P$1)") (class "Default")
      (node (ref "C20") (pin "1") (pinfunction "P$1_1") (pintype "bidirectional"))
      (node (ref "R10") (pin "1") (pinfunction "1_1") (pintype "bidirectional"))
      (node (ref "Y1") (pin "2") (pinfunction "2_2") (pintype "passive"))
    )
    (net (code "35") (name "Net-(C27-P$1)") (class "Default")
      (node (ref "C27") (pin "1") (pinfunction "P$1_1") (pintype "bidirectional"))
      (node (ref "IC6") (pin "48") (pinfunction "VCAP1_48") (pintype "bidirectional"))
    )
    (net (code "36") (name "Net-(C28-P$1)") (class "Default")
      (node (ref "C28") (pin "1") (pinfunction "P$1_1") (pintype "bidirectional"))
      (node (ref "IC6") (pin "73") (pinfunction "VCAP2_73") (pintype "bidirectional"))
    )
    (net (code "37") (name "Net-(IC1-PG)") (class "Default")
      (node (ref "IC1") (pin "4") (pinfunction "PG_4") (pintype "output"))
      (node (ref "R1") (pin "1") (pinfunction "1_1") (pintype "bidirectional"))
    )
    (net (code "38") (name "Net-(IC1-SW-Pad1)") (class "Default")
      (node (ref "IC1") (pin "1") (pinfunction "SW_1") (pintype "output"))
      (node (ref "IC1") (pin "2") (pinfunction "SW_2") (pintype "output"))
      (node (ref "IC1") (pin "3") (pinfunction "SW_3") (pintype "output"))
      (node (ref "L1") (pin "2") (pinfunction "2_2") (pintype "passive"))
    )
    (net (code "39") (name "Net-(LED1-A)") (class "Default")
      (node (ref "LED1") (pin "2") (pinfunction "A_2") (pintype "bidirectional"))
      (node (ref "R2") (pin "1") (pinfunction "1_1") (pintype "bidirectional"))
    )
    (net (code "40") (name "Net-(LED2-A)") (class "Default")
      (node (ref "LED2") (pin "2") (pinfunction "A_2") (pintype "bidirectional"))
      (node (ref "R5") (pin "1") (pinfunction "1_1") (pintype "bidirectional"))
    )
    (net (code "41") (name "Net-(LED3-A)") (class "Default")
      (node (ref "LED3") (pin "2") (pinfunction "A_2") (pintype "bidirectional"))
      (node (ref "R12") (pin "1") (pinfunction "1_1") (pintype "bidirectional"))
    )
    (net (code "42") (name "Net-(Q2-E)") (class "Default")
      (node (ref "Q2") (pin "2") (pinfunction "E_2") (pintype "power_in"))
      (node (ref "R5") (pin "2") (pinfunction "2_2") (pintype "bidirectional"))
    )
    (net (code "43") (name "Net-(Q3-E)") (class "Default")
      (node (ref "Q3") (pin "2") (pinfunction "E_2") (pintype "power_in"))
      (node (ref "R12") (pin "2") (pinfunction "2_2") (pintype "bidirectional"))
    )
    (net (code "44") (name "OSC32_IN") (class "Default")
      (node (ref "IC6") (pin "8") (pinfunction "PC14-OSC32_IN_8") (pintype "bidirectional"))
      (node (ref "R9") (pin "2") (pinfunction "2_2") (pintype "bidirectional"))
    )
    (net (code "45") (name "OSC32_OUT") (class "Default")
      (node (ref "IC6") (pin "9") (pinfunction "PC15-OSC32_OUT_9") (pintype "bidirectional"))
      (node (ref "R10") (pin "2") (pinfunction "2_2") (pintype "bidirectional"))
    )
    (net (code "46") (name "OSC_IN") (class "Default")
      (node (ref "C18") (pin "1") (pinfunction "P$1_1") (pintype "bidirectional"))
      (node (ref "IC6") (pin "12") (pinfunction "PH0-OSC_IN_12") (pintype "bidirectional"))
      (node (ref "Y2") (pin "1") (pinfunction "IN_1") (pintype "bidirectional"))
    )
    (net (code "47") (name "OSC_OUT") (class "Default")
      (node (ref "IC6") (pin "13") (pinfunction "PH1-OSC_OUT_13") (pintype "bidirectional"))
      (node (ref "R8") (pin "2") (pinfunction "2_2") (pintype "bidirectional"))
    )
    (net (code "48") (name "PWM11") (class "Default")
      (node (ref "IC6") (pin "39") (pinfunction "PE9_39") (pintype "bidirectional"))
      (node (ref "SV2") (pin "6") (pinfunction "6_6") (pintype "passive"))
    )
    (net (code "49") (name "PWM12") (class "Default")
      (node (ref "IC6") (pin "41") (pinfunction "PE11_41") (pintype "bidirectional"))
      (node (ref "SV2") (pin "5") (pinfunction "5_5") (pintype "passive"))
    )
    (net (code "50") (name "PWM13{slash}LCD_DE") (class "Default")
      (node (ref "IC6") (pin "43") (pinfunction "PE13_43") (pintype "bidirectional"))
      (node (ref "SV3") (pin "3") (pinfunction "3_3") (pintype "passive"))
    )
    (net (code "51") (name "PWM14{slash}LCD_CLK") (class "Default")
      (node (ref "IC6") (pin "44") (pinfunction "PE14_44") (pintype "bidirectional"))
      (node (ref "Q3") (pin "1") (pinfunction "B_1") (pintype "input"))
    )
    (net (code "52") (name "PWM23") (class "Default")
      (node (ref "IC6") (pin "46") (pinfunction "PB10_46") (pintype "bidirectional"))
      (node (ref "SV4") (pin "6") (pinfunction "6_6") (pintype "passive"))
    )
    (net (code "53") (name "PWM24") (class "Default")
      (node (ref "IC6") (pin "47") (pinfunction "PB11_47") (pintype "bidirectional"))
      (node (ref "SV4") (pin "5") (pinfunction "5_5") (pintype "passive"))
    )
    (net (code "54") (name "PWM31{slash}PWM82{slash}USART6_TX") (class "Default")
      (node (ref "IC6") (pin "63") (pinfunction "PC6_63") (pintype "bidirectional"))
      (node (ref "SV10") (pin "3") (pinfunction "3_3") (pintype "passive"))
    )
    (net (code "55") (name "PWM32{slash}PWM82{slash}USART6_RX") (class "Default")
      (node (ref "IC6") (pin "64") (pinfunction "PC7_64") (pintype "bidirectional"))
      (node (ref "SV10") (pin "1") (pinfunction "1_1") (pintype "passive"))
    )
    (net (code "56") (name "PWM32{slash}SPI3,6_MOSI") (class "Default")
      (node (ref "IC6") (pin "91") (pinfunction "PB5_91") (pintype "bidirectional"))
      (node (ref "SV9") (pin "4") (pinfunction "4_4") (pintype "passive"))
    )
    (net (code "57") (name "PWM33") (class "Default")
      (node (ref "IC6") (pin "34") (pinfunction "PB0_34") (pintype "bidirectional"))
      (node (ref "SV1") (pin "6") (pinfunction "6_6") (pintype "passive"))
    )
    (net (code "58") (name "PWM34") (class "Default")
      (node (ref "IC6") (pin "35") (pinfunction "PB1_35") (pintype "bidirectional"))
      (node (ref "SV1") (pin "5") (pinfunction "5_5") (pintype "passive"))
    )
    (net (code "59") (name "PWM41{slash}I2C1_SCL{slash}I2C4_SCL") (class "Default")
      (node (ref "IC6") (pin "92") (pinfunction "PB6_92") (pintype "bidirectional"))
      (node (ref "SV9") (pin "5") (pinfunction "5_5") (pintype "passive"))
    )
    (net (code "60") (name "PWM41{slash}I2C4_SCL") (class "Default")
      (node (ref "IC6") (pin "59") (pinfunction "PD12_59") (pintype "bidirectional"))
      (node (ref "SV11") (pin "6") (pinfunction "6_6") (pintype "passive"))
    )
    (net (code "61") (name "PWM42{slash}I2C1_SDA{slash}I2C4_SDA") (class "Default")
      (node (ref "IC6") (pin "93") (pinfunction "PB7_93") (pintype "bidirectional"))
      (node (ref "SV9") (pin "6") (pinfunction "6_6") (pintype "passive"))
    )
    (net (code "62") (name "PWM42{slash}I2C4_SDA") (class "Default")
      (node (ref "IC6") (pin "60") (pinfunction "PD13_60") (pintype "bidirectional"))
      (node (ref "SV10") (pin "5") (pinfunction "5_5") (pintype "passive"))
    )
    (net (code "63") (name "PWM43") (class "Default")
      (node (ref "IC6") (pin "61") (pinfunction "PD14_61") (pintype "bidirectional"))
      (node (ref "SV5") (pin "6") (pinfunction "6_6") (pintype "passive"))
    )
    (net (code "64") (name "PWM44") (class "Default")
      (node (ref "IC6") (pin "62") (pinfunction "PD15_62") (pintype "bidirectional"))
      (node (ref "SV5") (pin "5") (pinfunction "5_5") (pintype "passive"))
    )
    (net (code "65") (name "PWM101{slash}I2C1_SCL{slash}I2C4_SCL") (class "Default")
      (node (ref "IC6") (pin "95") (pinfunction "PB8_95") (pintype "bidirectional"))
      (node (ref "SV8") (pin "2") (pinfunction "2_2") (pintype "passive"))
    )
    (net (code "66") (name "PWM111{slash}I2C1_SDA{slash}I2C4_SDA") (class "Default")
      (node (ref "IC6") (pin "96") (pinfunction "PB9_96") (pintype "bidirectional"))
      (node (ref "SV8") (pin "3") (pinfunction "3_3") (pintype "passive"))
    )
    (net (code "67") (name "Q_GPIO") (class "Default")
      (node (ref "Q1") (pin "3") (pinfunction "D_3") (pintype "passive"))
      (node (ref "SV8") (pin "1") (pinfunction "1_1") (pintype "passive"))
    )
    (net (code "68") (name "RST_PIN") (class "Default")
      (node (ref "D4") (pin "1") (pinfunction "A_1") (pintype "passive"))
      (node (ref "SV9") (pin "8") (pinfunction "8_8") (pintype "passive"))
    )
    (net (code "69") (name "SDMMC1_CK") (class "Default")
      (node (ref "IC6") (pin "80") (pinfunction "PC12_80") (pintype "bidirectional"))
      (node (ref "X1") (pin "5") (pinfunction "CLK_5") (pintype "bidirectional"))
    )
    (net (code "70") (name "SDMMC1_CMD") (class "Default")
      (node (ref "IC6") (pin "83") (pinfunction "PD2_83") (pintype "bidirectional"))
      (node (ref "X1") (pin "3") (pinfunction "CMD_3") (pintype "bidirectional"))
    )
    (net (code "71") (name "SDMMC1_D0") (class "Default")
      (node (ref "IC6") (pin "65") (pinfunction "PC8_65") (pintype "bidirectional"))
      (node (ref "X1") (pin "7") (pinfunction "DAT0_7") (pintype "bidirectional"))
    )
    (net (code "72") (name "SDMMC1_D1") (class "Default")
      (node (ref "IC6") (pin "66") (pinfunction "PC9_66") (pintype "bidirectional"))
      (node (ref "X1") (pin "8") (pinfunction "DAT1_8") (pintype "bidirectional"))
    )
    (net (code "73") (name "SDMMC1_D2") (class "Default")
      (node (ref "IC6") (pin "78") (pinfunction "PC10_78") (pintype "bidirectional"))
      (node (ref "X1") (pin "1") (pinfunction "DAT2_1") (pintype "bidirectional"))
    )
    (net (code "74") (name "SDMMC1_D3") (class "Default")
      (node (ref "IC6") (pin "79") (pinfunction "PC11_79") (pintype "bidirectional"))
      (node (ref "X1") (pin "2") (pinfunction "DAT3_2") (pintype "bidirectional"))
    )
    (net (code "75") (name "SPI1_MISO") (class "Default")
      (node (ref "IC3") (pin "9") (pinfunction "AD0/SDO_9") (pintype "bidirectional"))
      (node (ref "IC6") (pin "30") (pinfunction "PA6_30") (pintype "bidirectional"))
    )
    (net (code "76") (name "SPI1_MOSI") (class "Default")
      (node (ref "IC3") (pin "24") (pinfunction "SDA/SDI_24") (pintype "bidirectional"))
      (node (ref "IC6") (pin "31") (pinfunction "PA7_31") (pintype "bidirectional"))
    )
    (net (code "77") (name "SPI1_SCK") (class "Default")
      (node (ref "IC3") (pin "23") (pinfunction "SCL/SCLK_23") (pintype "bidirectional"))
      (node (ref "IC6") (pin "29") (pinfunction "PA5_29") (pintype "bidirectional"))
    )
    (net (code "78") (name "SPI2_MISO") (class "Default")
      (node (ref "IC6") (pin "53") (pinfunction "PB14_2_53") (pintype "bidirectional"))
      (node (ref "SV11") (pin "1") (pinfunction "1_1") (pintype "passive"))
    )
    (net (code "79") (name "SPI2_MOSI") (class "Default")
      (node (ref "IC6") (pin "54") (pinfunction "PB15_54") (pintype "bidirectional"))
      (node (ref "SV11") (pin "2") (pinfunction "2_2") (pintype "passive"))
    )
    (net (code "80") (name "SPI2_SCK") (class "Default")
      (node (ref "IC6") (pin "84") (pinfunction "PD3_84") (pintype "bidirectional"))
      (node (ref "SV9") (pin "1") (pinfunction "1_1") (pintype "passive"))
    )
    (net (code "81") (name "SPI4_MISO") (class "Default")
      (node (ref "IC4") (pin "6") (pinfunction "SDO_6") (pintype "bidirectional"))
      (node (ref "IC5") (pin "5") (pinfunction "SDO_5") (pintype "bidirectional"))
      (node (ref "IC6") (pin "4") (pinfunction "PE5_4") (pintype "bidirectional"))
    )
    (net (code "82") (name "SPI4_MOSI") (class "Default")
      (node (ref "IC4") (pin "5") (pinfunction "SDA/SI_5") (pintype "bidirectional"))
      (node (ref "IC5") (pin "3") (pinfunction "SDI_3") (pintype "bidirectional"))
      (node (ref "IC6") (pin "5") (pinfunction "PE6_5") (pintype "bidirectional"))
    )
    (net (code "83") (name "SPI4_SCK") (class "Default")
      (node (ref "IC4") (pin "3") (pinfunction "SCL/SK_3") (pintype "bidirectional"))
      (node (ref "IC5") (pin "4") (pinfunction "SCK_4") (pintype "bidirectional"))
      (node (ref "IC6") (pin "1") (pinfunction "PE2_1") (pintype "bidirectional"))
    )
    (net (code "84") (name "UART2_RX(MAG_CS)") (class "Default")
      (node (ref "IC4") (pin "2") (pinfunction "~{CS}_2") (pintype "bidirectional"))
      (node (ref "IC6") (pin "25") (pinfunction "PA3_25") (pintype "bidirectional"))
    )
    (net (code "85") (name "UART2_TX(P+T_CS)") (class "Default")
      (node (ref "IC5") (pin "2") (pinfunction "~{CS}_2") (pintype "input"))
      (node (ref "IC6") (pin "24") (pinfunction "PA2_24") (pintype "bidirectional"))
    )
    (net (code "86") (name "UART4_RX") (class "Default")
      (node (ref "IC6") (pin "23") (pinfunction "PA1_23") (pintype "bidirectional"))
      (node (ref "X4") (pin "3") (pinfunction "3_3") (pintype "bidirectional"))
    )
    (net (code "87") (name "UART4_TX") (class "Default")
      (node (ref "IC6") (pin "22") (pinfunction "PA0-WKUP_22") (pintype "bidirectional"))
      (node (ref "X4") (pin "4") (pinfunction "4_4") (pintype "bidirectional"))
    )
    (net (code "88") (name "UART5_RX") (class "Default")
      (node (ref "IC6") (pin "51") (pinfunction "PB12_51") (pintype "bidirectional"))
      (node (ref "SV7") (pin "4") (pinfunction "4_4") (pintype "passive"))
    )
    (net (code "89") (name "UART5_TX") (class "Default")
      (node (ref "IC6") (pin "52") (pinfunction "PB13_2_52") (pintype "bidirectional"))
      (node (ref "SV7") (pin "3") (pinfunction "3_3") (pintype "passive"))
    )
    (net (code "90") (name "UART7_RX") (class "Default")
      (node (ref "IC6") (pin "37") (pinfunction "PE7_37") (pintype "bidirectional"))
      (node (ref "SV6") (pin "4") (pinfunction "4_4") (pintype "passive"))
    )
    (net (code "91") (name "UART7_TX") (class "Default")
      (node (ref "IC6") (pin "38") (pinfunction "PE8_38") (pintype "bidirectional"))
      (node (ref "SV6") (pin "3") (pinfunction "3_3") (pintype "passive"))
    )
    (net (code "92") (name "UART8_RX") (class "Default")
      (node (ref "IC6") (pin "97") (pinfunction "PE0_97") (pintype "bidirectional"))
      (node (ref "X3") (pin "3") (pinfunction "3_3") (pintype "bidirectional"))
    )
    (net (code "93") (name "UART8_TX") (class "Default")
      (node (ref "IC6") (pin "98") (pinfunction "PE1_98") (pintype "bidirectional"))
      (node (ref "X3") (pin "4") (pinfunction "4_4") (pintype "bidirectional"))
    )
    (net (code "94") (name "USART1_CK") (class "Default")
      (node (ref "IC6") (pin "67") (pinfunction "PA8_67") (pintype "bidirectional"))
    )
    (net (code "95") (name "USART2_CK") (class "Default")
      (node (ref "IC6") (pin "88") (pinfunction "PD7_88") (pintype "bidirectional"))
    )
    (net (code "96") (name "USART2_RX{slash}SPI3_MOSI") (class "Default")
      (node (ref "IC6") (pin "87") (pinfunction "PD6_87") (pintype "bidirectional"))
    )
    (net (code "97") (name "USART2_TX") (class "Default")
      (node (ref "IC6") (pin "86") (pinfunction "PD5_86") (pintype "bidirectional"))
    )
    (net (code "98") (name "USART3_CK") (class "Default")
      (node (ref "IC6") (pin "57") (pinfunction "PD10_57") (pintype "bidirectional"))
    )
    (net (code "99") (name "USART3_CTS") (class "Default")
      (node (ref "IC6") (pin "58") (pinfunction "PD11_58") (pintype "bidirectional"))
    )
    (net (code "100") (name "USART3_RX") (class "Default")
      (node (ref "IC6") (pin "56") (pinfunction "PD9_56") (pintype "bidirectional"))
    )
    (net (code "101") (name "USART3_TX") (class "Default")
      (node (ref "IC6") (pin "55") (pinfunction "PD8_55") (pintype "bidirectional"))
    )
    (net (code "102") (name "USB_5V") (class "Default")
      (node (ref "D3") (pin "1") (pinfunction "A_1") (pintype "passive"))
      (node (ref "X2") (pin "1") (pinfunction "1_1") (pintype "input"))
    )
    (net (code "103") (name "USB_DM") (class "Default")
      (node (ref "IC6") (pin "70") (pinfunction "PA11_70") (pintype "bidirectional"))
      (node (ref "X2") (pin "2") (pinfunction "2_2") (pintype "input"))
    )
    (net (code "104") (name "USB_DP") (class "Default")
      (node (ref "IC6") (pin "71") (pinfunction "PA12_71") (pintype "bidirectional"))
      (node (ref "X2") (pin "3") (pinfunction "3_3") (pintype "input"))
    )
    (net (code "105") (name "USB_ID") (class "Default")
      (node (ref "IC6") (pin "69") (pinfunction "PA10_69") (pintype "bidirectional"))
      (node (ref "X2") (pin "4") (pinfunction "4_4") (pintype "input"))
    )
    (net (code "106") (name "USB_VBUS") (class "Default")
      (node (ref "IC6") (pin "68") (pinfunction "PA9_68") (pintype "bidirectional"))
    )
    (net (code "107") (name "VIN") (class "Default")
      (node (ref "D1") (pin "1") (pinfunction "A_1") (pintype "passive"))
      (node (ref "R4") (pin "2") (pinfunction "2_2") (pintype "bidirectional"))
      (node (ref "SV1") (pin "3") (pinfunction "3_3") (pintype "passive"))
      (node (ref "SV1") (pin "4") (pinfunction "4_4") (pintype "passive"))
      (node (ref "SV2") (pin "3") (pinfunction "3_3") (pintype "passive"))
      (node (ref "SV2") (pin "4") (pinfunction "4_4") (pintype "passive"))
      (node (ref "SV3") (pin "2") (pinfunction "2_2") (pintype "passive"))
      (node (ref "SV4") (pin "3") (pinfunction "3_3") (pintype "passive"))
      (node (ref "SV4") (pin "4") (pinfunction "4_4") (pintype "passive"))
      (node (ref "SV5") (pin "3") (pinfunction "3_3") (pintype "passive"))
      (node (ref "SV5") (pin "4") (pinfunction "4_4") (pintype "passive"))
    )
    (net (code "108") (name "unconnected-(IC3-~{CS}-Pad22)") (class "Default")
      (node (ref "IC3") (pin "22") (pinfunction "~{CS}_22") (pintype "bidirectional"))
    )
    (net (code "109") (name "unconnected-(IC4-DRDY-Pad1)") (class "Default")
      (node (ref "IC4") (pin "1") (pinfunction "DRDY_1") (pintype "bidirectional"))
    )
    (net (code "110") (name "unconnected-(IC4-RSV-Pad4)") (class "Default")
      (node (ref "IC4") (pin "4") (pinfunction "RSV_4") (pintype "bidirectional"))
    )
    (net (code "111") (name "unconnected-(IC4-TST1-Pad14)") (class "Default")
      (node (ref "IC4") (pin "14") (pinfunction "TST1_14") (pintype "bidirectional"))
    )
    (net (code "112") (name "unconnected-(S2-PadP$1)") (class "Default")
      (node (ref "S2") (pin "P$1") (pinfunction "P$1_P$1") (pintype "bidirectional"))
    )
    (net (code "113") (name "unconnected-(S2-PadP$3)") (class "Default")
      (node (ref "S2") (pin "P$3") (pinfunction "P$3_P$3") (pintype "bidirectional"))
    )
    (net (code "114") (name "~{RST}") (class "Default")
      (node (ref "C21") (pin "1") (pinfunction "P$1_1") (pintype "bidirectional"))
      (node (ref "D4") (pin "2") (pinfunction "C_2") (pintype "passive"))
      (node (ref "IC6") (pin "14") (pinfunction "~{RST}_14") (pintype "bidirectional"))
      (node (ref "R11") (pin "1") (pinfunction "1_1") (pintype "bidirectional"))
      (node (ref "S2") (pin "P$2") (pinfunction "P$2_P$2") (pintype "bidirectional"))
    )
  )
)
